# design.net
KiCad netlist of a schematic drawn in Altium Designer
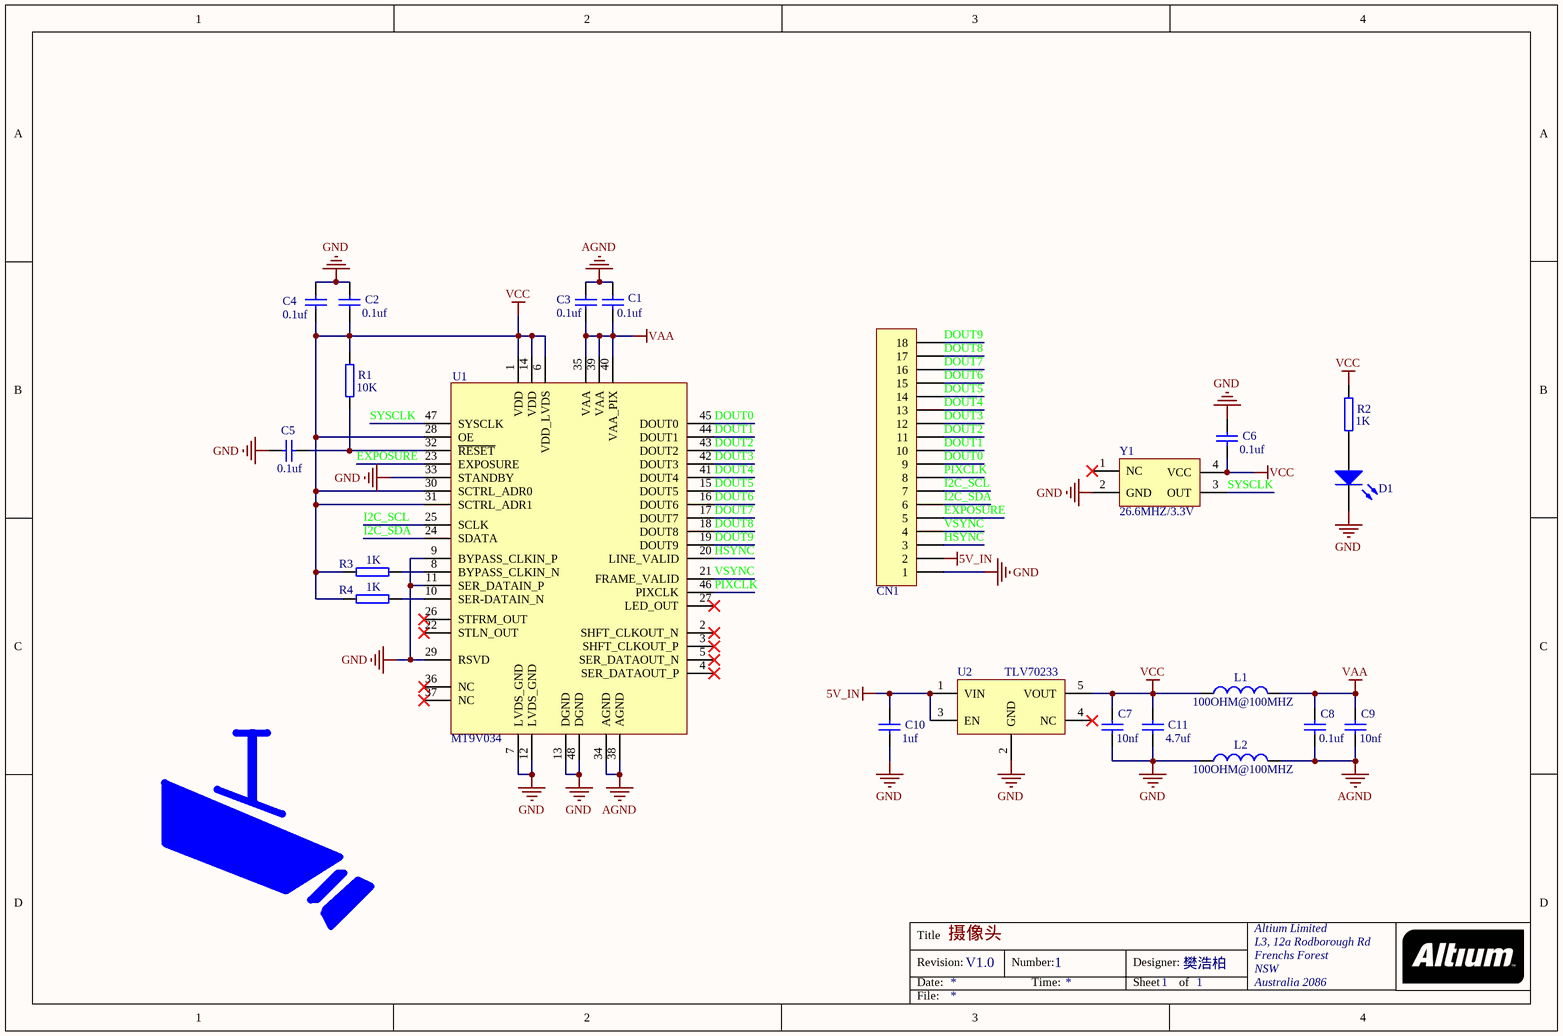
[diagram p0: 摄像头.SchDoc]

(export (version "E")
  (design (tool "Eeschema 10.0.6"))
  (components
    (comp (ref "C1") (value "0.1uf") (footprint "CAP-0402") (libsource (lib "Connectors") (part "Cap")))
    (comp (ref "C2") (value "0.1uf") (footprint "CAP-0402") (libsource (lib "Connectors") (part "Cap")))
    (comp (ref "C3") (value "0.1uf") (footprint "CAP-0402") (libsource (lib "Connectors") (part "Cap")))
    (comp (ref "C4") (value "0.1uf") (footprint "CAP-0402") (libsource (lib "Connectors") (part "Cap")))
    (comp (ref "C5") (value "0.1uf") (footprint "CAP-0402") (libsource (lib "Connectors") (part "Cap")))
    (comp (ref "C6") (value "0.1uf") (footprint "CAP-0402") (libsource (lib "Connectors") (part "Cap")))
    (comp (ref "C7") (value "10nf") (footprint "CAP-0402") (libsource (lib "Connectors") (part "Cap")))
    (comp (ref "C8") (value "0.1uf") (footprint "CAP-0402") (libsource (lib "Connectors") (part "Cap")))
    (comp (ref "C9") (value "10nf") (footprint "CAP-0402") (libsource (lib "Connectors") (part "Cap")))
    (comp (ref "C10") (value "1uf") (footprint "CAP-0402") (libsource (lib "Connectors") (part "Cap")))
    (comp (ref "C11") (value "4.7uf") (footprint "CAP-0402") (libsource (lib "Connectors") (part "Cap")))
    (comp (ref "Camera") (value "Camera") (footprint "Camera") (libsource (lib "Devices") (part "Camera")))
    (comp (ref "CN1")
      (value "CON-18X1")
      (footprint "HEADER-FPC-ZIF-SMD-Horizontal-0.5-18")
      (libsource (lib "Connectors-Header") (part "CON-18X1"))
    )
    (comp (ref "D1") (value "LED") (footprint "LED-BLU-0603") (libsource (lib "Connectors") (part "LED")))
    (comp (ref "L1")
      (value "100OHM@100MHZ")
      (footprint "Chip Inductor-0402_100505")
      (libsource (lib "Connectors") (part "Inductor"))
    )
    (comp (ref "L2")
      (value "100OHM@100MHZ")
      (footprint "Chip Inductor-0402_100505")
      (libsource (lib "Connectors") (part "Inductor"))
    )
    (comp (ref "R1") (value "10K") (footprint "RES-0402") (libsource (lib "Connectors") (part "Res")))
    (comp (ref "R2") (value "1K") (footprint "RES-0402") (libsource (lib "Connectors") (part "Res")))
    (comp (ref "R3") (value "1K") (footprint "RES-0402") (libsource (lib "Connectors") (part "Res")))
    (comp (ref "R4") (value "1K") (footprint "RES-0402") (libsource (lib "Connectors") (part "Res")))
    (comp (ref "U1")
      (value "MT9V034")
      (footprint "CLCC-48-11.43X11.43")
      (libsource (lib "Devices") (part "MT9V034"))
    )
    (comp (ref "U2")
      (value "TLV70233")
      (footprint "SOT-23-5")
      (fields (field (name "PUBLISHER") "Altium Limited"))
      (libsource (lib "Devices") (part "LDO"))
    )
    (comp (ref "Y1")
      (value "26.6MHZ/3.3V")
      (footprint "XTAL-OSC-3225")
      (libsource (lib "Connectors") (part "XTAL-OSC"))
    )
  )
  (nets
    (net (code "1") (name "/DOUT0") (class "Default")
      (node (ref "CN1") (pin "9") (pinfunction "9_9") (pintype "passive"))
      (node (ref "U1") (pin "45") (pinfunction "DOUT0_45") (pintype "passive"))
    )
    (net (code "2") (name "/DOUT1") (class "Default")
      (node (ref "CN1") (pin "10") (pinfunction "10_10") (pintype "passive"))
      (node (ref "U1") (pin "44") (pinfunction "DOUT1_44") (pintype "passive"))
    )
    (net (code "3") (name "/DOUT2") (class "Default")
      (node (ref "CN1") (pin "11") (pinfunction "11_11") (pintype "passive"))
      (node (ref "U1") (pin "43") (pinfunction "DOUT2_43") (pintype "passive"))
    )
    (net (code "4") (name "/DOUT3") (class "Default")
      (node (ref "CN1") (pin "12") (pinfunction "12_12") (pintype "passive"))
      (node (ref "U1") (pin "42") (pinfunction "DOUT3_42") (pintype "passive"))
    )
    (net (code "5") (name "/DOUT4") (class "Default")
      (node (ref "CN1") (pin "13") (pinfunction "13_13") (pintype "passive"))
      (node (ref "U1") (pin "41") (pinfunction "DOUT4_41") (pintype "passive"))
    )
    (net (code "6") (name "/DOUT5") (class "Default")
      (node (ref "CN1") (pin "14") (pinfunction "14_14") (pintype "passive"))
      (node (ref "U1") (pin "15") (pinfunction "DOUT5_15") (pintype "passive"))
    )
    (net (code "7") (name "/DOUT6") (class "Default")
      (node (ref "CN1") (pin "15") (pinfunction "15_15") (pintype "passive"))
      (node (ref "U1") (pin "16") (pinfunction "DOUT6_16") (pintype "passive"))
    )
    (net (code "8") (name "/DOUT7") (class "Default")
      (node (ref "CN1") (pin "16") (pinfunction "16_16") (pintype "passive"))
      (node (ref "U1") (pin "17") (pinfunction "DOUT7_17") (pintype "passive"))
    )
    (net (code "9") (name "/DOUT8") (class "Default")
      (node (ref "CN1") (pin "17") (pinfunction "17_17") (pintype "passive"))
      (node (ref "U1") (pin "18") (pinfunction "DOUT8_18") (pintype "passive"))
    )
    (net (code "10") (name "/DOUT9") (class "Default")
      (node (ref "CN1") (pin "18") (pinfunction "18_18") (pintype "passive"))
      (node (ref "U1") (pin "19") (pinfunction "DOUT9_19") (pintype "passive"))
    )
    (net (code "11") (name "/EXPOSURE") (class "Default")
      (node (ref "CN1") (pin "5") (pinfunction "5_5") (pintype "passive"))
      (node (ref "U1") (pin "23") (pinfunction "EXPOSURE_23") (pintype "passive"))
    )
    (net (code "12") (name "/HSYNC") (class "Default")
      (node (ref "CN1") (pin "3") (pinfunction "3_3") (pintype "passive"))
      (node (ref "U1") (pin "20") (pinfunction "LINE_VALID_20") (pintype "passive"))
    )
    (net (code "13") (name "/I2C_SCL") (class "Default")
      (node (ref "CN1") (pin "7") (pinfunction "7_7") (pintype "passive"))
      (node (ref "U1") (pin "25") (pinfunction "SCLK_25") (pintype "passive"))
    )
    (net (code "14") (name "/I2C_SDA") (class "Default")
      (node (ref "CN1") (pin "6") (pinfunction "6_6") (pintype "passive"))
      (node (ref "U1") (pin "24") (pinfunction "SDATA_24") (pintype "passive"))
    )
    (net (code "15") (name "/PIXCLK") (class "Default")
      (node (ref "CN1") (pin "8") (pinfunction "8_8") (pintype "passive"))
      (node (ref "U1") (pin "46") (pinfunction "PIXCLK_46") (pintype "passive"))
    )
    (net (code "16") (name "/SYSCLK") (class "Default")
      (node (ref "U1") (pin "47") (pinfunction "SYSCLK_47") (pintype "passive"))
      (node (ref "Y1") (pin "3") (pinfunction "OUT_3") (pintype "passive"))
    )
    (net (code "17") (name "/VSYNC") (class "Default")
      (node (ref "CN1") (pin "4") (pinfunction "4_4") (pintype "passive"))
      (node (ref "U1") (pin "21") (pinfunction "FRAME_VALID_21") (pintype "passive"))
    )
    (net (code "18") (name "5V_IN") (class "Default")
      (node (ref "C10") (pin "1") (pinfunction "1_1") (pintype "passive"))
      (node (ref "CN1") (pin "2") (pinfunction "2_2") (pintype "passive"))
      (node (ref "U2") (pin "1") (pinfunction "VIN_1") (pintype "passive"))
      (node (ref "U2") (pin "3") (pinfunction "EN_3") (pintype "passive"))
    )
    (net (code "19") (name "AGND") (class "Default")
      (node (ref "C1") (pin "1") (pinfunction "1_1") (pintype "passive"))
      (node (ref "C3") (pin "2") (pinfunction "2_2") (pintype "passive"))
      (node (ref "C8") (pin "2") (pinfunction "2_2") (pintype "passive"))
      (node (ref "C9") (pin "2") (pinfunction "2_2") (pintype "passive"))
      (node (ref "L2") (pin "2") (pinfunction "2_2") (pintype "passive"))
      (node (ref "U1") (pin "34") (pinfunction "AGND_34") (pintype "passive"))
      (node (ref "U1") (pin "38") (pinfunction "AGND_38") (pintype "passive"))
    )
    (net (code "20") (name "GND") (class "Default")
      (node (ref "C10") (pin "2") (pinfunction "2_2") (pintype "passive"))
      (node (ref "C11") (pin "2") (pinfunction "2_2") (pintype "passive"))
      (node (ref "C2") (pin "1") (pinfunction "1_1") (pintype "passive"))
      (node (ref "C4") (pin "1") (pinfunction "1_1") (pintype "passive"))
      (node (ref "C5") (pin "1") (pinfunction "1_1") (pintype "passive"))
      (node (ref "C6") (pin "1") (pinfunction "1_1") (pintype "passive"))
      (node (ref "C7") (pin "2") (pinfunction "2_2") (pintype "passive"))
      (node (ref "CN1") (pin "1") (pinfunction "1_1") (pintype "passive"))
      (node (ref "D1") (pin "K") (pinfunction "2_K") (pintype "passive"))
      (node (ref "L2") (pin "1") (pinfunction "1_1") (pintype "passive"))
      (node (ref "U1") (pin "11") (pinfunction "SER_DATAIN_P_11") (pintype "passive"))
      (node (ref "U1") (pin "12") (pinfunction "LVDS_GND_12") (pintype "passive"))
      (node (ref "U1") (pin "13") (pinfunction "DGND_13") (pintype "passive"))
      (node (ref "U1") (pin "29") (pinfunction "RSVD_29") (pintype "passive"))
      (node (ref "U1") (pin "33") (pinfunction "STANDBY_33") (pintype "passive"))
      (node (ref "U1") (pin "48") (pinfunction "DGND_48") (pintype "passive"))
      (node (ref "U1") (pin "7") (pinfunction "LVDS_GND_7") (pintype "passive"))
      (node (ref "U1") (pin "9") (pinfunction "BYPASS_CLKIN_P_9") (pintype "passive"))
      (node (ref "U2") (pin "2") (pinfunction "GND_2") (pintype "passive"))
      (node (ref "Y1") (pin "2") (pinfunction "GND_2") (pintype "passive"))
    )
    (net (code "21") (name "Net-(D1-1)") (class "Default")
      (node (ref "D1") (pin "A") (pinfunction "1_A") (pintype "passive"))
      (node (ref "R2") (pin "1") (pinfunction "1_1") (pintype "passive"))
    )
    (net (code "22") (name "Net-(U1-BYPASS_CLKIN_N)") (class "Default")
      (node (ref "R3") (pin "2") (pinfunction "2_2") (pintype "passive"))
      (node (ref "U1") (pin "8") (pinfunction "BYPASS_CLKIN_N_8") (pintype "passive"))
    )
    (net (code "23") (name "Net-(U1-SER-DATAIN_N)") (class "Default")
      (node (ref "R4") (pin "2") (pinfunction "2_2") (pintype "passive"))
      (node (ref "U1") (pin "10") (pinfunction "SER-DATAIN_N_10") (pintype "passive"))
    )
    (net (code "24") (name "Net-(U1-~{RESET})") (class "Default")
      (node (ref "C5") (pin "2") (pinfunction "2_2") (pintype "passive"))
      (node (ref "R1") (pin "1") (pinfunction "1_1") (pintype "passive"))
      (node (ref "U1") (pin "32") (pinfunction "~{RESET}_32") (pintype "passive"))
    )
    (net (code "25") (name "VAA") (class "Default")
      (node (ref "C1") (pin "2") (pinfunction "2_2") (pintype "passive"))
      (node (ref "C3") (pin "1") (pinfunction "1_1") (pintype "passive"))
      (node (ref "C8") (pin "1") (pinfunction "1_1") (pintype "passive"))
      (node (ref "C9") (pin "1") (pinfunction "1_1") (pintype "passive"))
      (node (ref "L1") (pin "2") (pinfunction "2_2") (pintype "passive"))
      (node (ref "U1") (pin "35") (pinfunction "VAA_35") (pintype "passive"))
      (node (ref "U1") (pin "39") (pinfunction "VAA_39") (pintype "passive"))
      (node (ref "U1") (pin "40") (pinfunction "VAA_PIX_40") (pintype "passive"))
    )
    (net (code "26") (name "VCC") (class "Default")
      (node (ref "C11") (pin "1") (pinfunction "1_1") (pintype "passive"))
      (node (ref "C2") (pin "2") (pinfunction "2_2") (pintype "passive"))
      (node (ref "C4") (pin "2") (pinfunction "2_2") (pintype "passive"))
      (node (ref "C6") (pin "2") (pinfunction "2_2") (pintype "passive"))
      (node (ref "C7") (pin "1") (pinfunction "1_1") (pintype "passive"))
      (node (ref "L1") (pin "1") (pinfunction "1_1") (pintype "passive"))
      (node (ref "R1") (pin "2") (pinfunction "2_2") (pintype "passive"))
      (node (ref "R2") (pin "2") (pinfunction "2_2") (pintype "passive"))
      (node (ref "R3") (pin "1") (pinfunction "1_1") (pintype "passive"))
      (node (ref "R4") (pin "1") (pinfunction "1_1") (pintype "passive"))
      (node (ref "U1") (pin "1") (pinfunction "VDD_1") (pintype "passive"))
      (node (ref "U1") (pin "14") (pinfunction "VDD_14") (pintype "passive"))
      (node (ref "U1") (pin "28") (pinfunction "OE_28") (pintype "passive"))
      (node (ref "U1") (pin "30") (pinfunction "SCTRL_ADR0_30") (pintype "passive"))
      (node (ref "U1") (pin "31") (pinfunction "SCTRL_ADR1_31") (pintype "passive"))
      (node (ref "U1") (pin "6") (pinfunction "VDD_LVDS_6") (pintype "passive"))
      (node (ref "U2") (pin "5") (pinfunction "VOUT_5") (pintype "passive"))
      (node (ref "Y1") (pin "4") (pinfunction "VCC_4") (pintype "passive"))
    )
    (net (code "27") (name "unconnected-(U1-LED_OUT-Pad27)") (class "Default")
      (node (ref "U1") (pin "27") (pinfunction "LED_OUT_27") (pintype "passive+no_connect"))
    )
    (net (code "28") (name "unconnected-(U1-NC-Pad36)") (class "Default")
      (node (ref "U1") (pin "36") (pinfunction "NC_36") (pintype "passive+no_connect"))
    )
    (net (code "29") (name "unconnected-(U1-NC-Pad37)") (class "Default")
      (node (ref "U1") (pin "37") (pinfunction "NC_37") (pintype "passive+no_connect"))
    )
    (net (code "30") (name "unconnected-(U1-SER_DATAOUT_N-Pad5)") (class "Default")
      (node (ref "U1") (pin "5") (pinfunction "SER_DATAOUT_N_5") (pintype "passive+no_connect"))
    )
    (net (code "31") (name "unconnected-(U1-SER_DATAOUT_P-Pad4)") (class "Default")
      (node (ref "U1") (pin "4") (pinfunction "SER_DATAOUT_P_4") (pintype "passive+no_connect"))
    )
    (net (code "32") (name "unconnected-(U1-SHFT_CLKOUT_N-Pad2)") (class "Default")
      (node (ref "U1") (pin "2") (pinfunction "SHFT_CLKOUT_N_2") (pintype "passive+no_connect"))
    )
    (net (code "33") (name "unconnected-(U1-SHFT_CLKOUT_P-Pad3)") (class "Default")
      (node (ref "U1") (pin "3") (pinfunction "SHFT_CLKOUT_P_3") (pintype "passive+no_connect"))
    )
    (net (code "34") (name "unconnected-(U1-STFRM_OUT-Pad26)") (class "Default")
      (node (ref "U1") (pin "26") (pinfunction "STFRM_OUT_26") (pintype "passive+no_connect"))
    )
    (net (code "35") (name "unconnected-(U1-STLN_OUT-Pad22)") (class "Default")
      (node (ref "U1") (pin "22") (pinfunction "STLN_OUT_22") (pintype "passive+no_connect"))
    )
    (net (code "36") (name "unconnected-(U2-NC-Pad4)") (class "Default")
      (node (ref "U2") (pin "4") (pinfunction "NC_4") (pintype "passive+no_connect"))
    )
    (net (code "37") (name "unconnected-(Y1-NC-Pad1)") (class "Default")
      (node (ref "Y1") (pin "1") (pinfunction "NC_1") (pintype "passive+no_connect"))
    )
  )
)
